# Power.net
KiCad netlist of a schematic drawn in Altium Designer
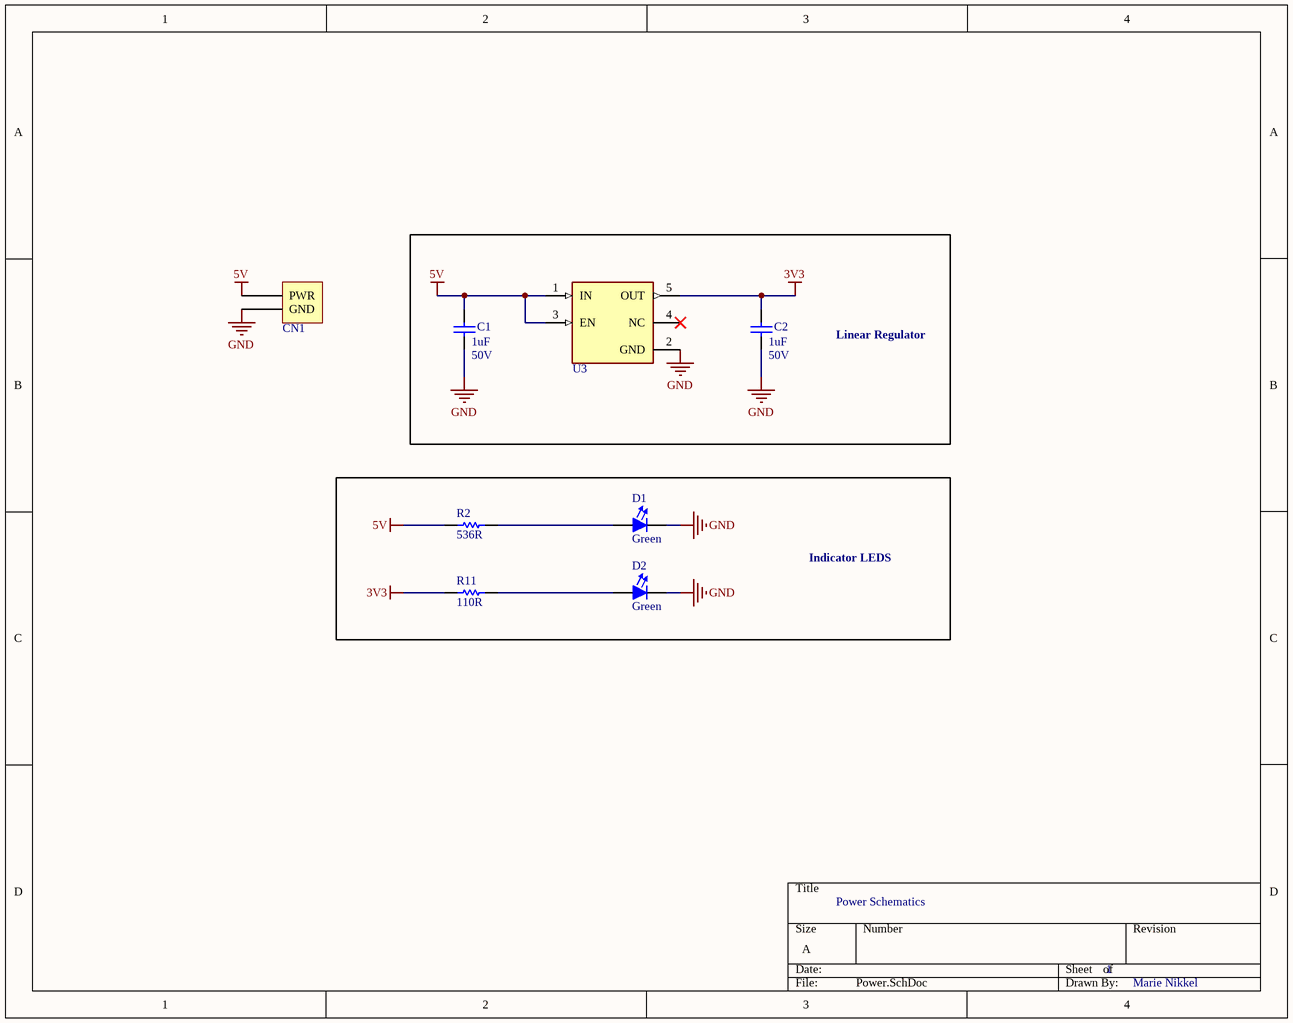
[diagram p0: Power.SchDoc]

(export (version "E")
  (design (tool "Eeschema 10.0.6"))
  (components
    (comp (ref "C1")
      (value "CL21B105KBFNNNG")
      (footprint "0803 CAP")
      (description "SAMSUNG ELECTRO-MECHANICS - CL21B105KBFNNNG - MLCC CAPACITORS")
      (fields
        (field (name "TOLERANCE") "10%")
        (field (name "CAPACITANCE") "1uF")
        (field (name "VOLTAGE") "50V")
      )
      (libsource (lib "AUVIC") (part "Symbol"))
    )
    (comp (ref "C2")
      (value "CL21B105KBFNNNG")
      (footprint "0803 CAP")
      (description "SAMSUNG ELECTRO-MECHANICS - CL21B105KBFNNNG - MLCC CAPACITORS")
      (fields
        (field (name "TOLERANCE") "10%")
        (field (name "CAPACITANCE") "1uF")
        (field (name "VOLTAGE") "50V")
      )
      (libsource (lib "AUVIC") (part "Symbol"))
    )
    (comp (ref "CN1")
      (value "Header, Female, 1x2, Right Angle, Pitch 0.118\" (3.00mm), THT")
      (footprint "New footprint 1")
      (description "Connector Header Through Hole, Right Angle 2 position")
      (libsource (lib "AUVIC") (part "Header, 1x2, Right Angle, Pitch 0.118{dblquote} (3.00mm), THT"))
    )
    (comp (ref "D1")
      (value "LT Q39G-Q1OO-25-1")
      (footprint "FP-LB_Q39E-MFG")
      (description "LED GREEN DIFFUSED 0603 SMD")
      (fields (field (name "COLOR") "Green"))
      (libsource (lib "") (part "Symbol_1"))
    )
    (comp (ref "D2")
      (value "LT Q39G-Q1OO-25-1")
      (footprint "FP-LB_Q39E-MFG")
      (description "LED GREEN DIFFUSED 0603 SMD")
      (fields (field (name "COLOR") "Green"))
      (libsource (lib "") (part "Symbol_1"))
    )
    (comp (ref "R2")
      (value "ERJ-3EKF5360V")
      (footprint "RESC1608X55X30NL15T15")
      (description "SMD Chip Resistor, 0603 [1608 Metric], 536 ohm, ERJ3EK Series, 75 V, Thick Film, 100 mW")
      (fields (field (name "TOLERANCE") "1%") (field (name "RESISTANCE") "536R"))
      (libsource (lib "AUVIC") (part "RES"))
    )
    (comp (ref "R11")
      (value "RC0603FR-07110RL")
      (footprint "RESC1608X55X25ML10T15")
      (description "RES SMD 110 OHM 1% 1/10W 0603")
      (fields (field (name "TOLERANCE") "1%") (field (name "RESISTANCE") "110R"))
      (libsource (lib "AUVIC") (part "RES"))
    )
    (comp (ref "U3")
      (value "TLV75533PDBVR")
      (footprint "FP-DBV0005A-IPC_B")
      (description "500-mA, high-PSRR, low-IQ, low-dropout voltage regulator with enable 5-SOT-23 -40 to 125")
      (libsource (lib "AUVIC") (part "bc27d4aa6bca38f00d7b0ca125c90e0"))
    )
  )
  (nets
    (net (code "1") (name "3V3") (class "Default")
      (node (ref "C2") (pin "1") (pinfunction "1_1") (pintype "passive"))
      (node (ref "R11") (pin "1") (pinfunction "1_1") (pintype "passive"))
      (node (ref "U3") (pin "5") (pinfunction "OUT_5") (pintype "output"))
    )
    (net (code "2") (name "5V") (class "Default")
      (node (ref "C1") (pin "1") (pinfunction "1_1") (pintype "passive"))
      (node (ref "CN1") (pin "2") (pinfunction "PWR_2") (pintype "passive"))
      (node (ref "R2") (pin "1") (pinfunction "1_1") (pintype "passive"))
      (node (ref "U3") (pin "1") (pinfunction "IN_1") (pintype "input"))
      (node (ref "U3") (pin "3") (pinfunction "EN_3") (pintype "input"))
    )
    (net (code "3") (name "GND") (class "Default")
      (node (ref "C1") (pin "2") (pinfunction "2_2") (pintype "passive"))
      (node (ref "C2") (pin "2") (pinfunction "2_2") (pintype "passive"))
      (node (ref "CN1") (pin "1") (pinfunction "GND_1") (pintype "passive"))
      (node (ref "D1") (pin "1") (pinfunction "Cathode_1") (pintype "passive"))
      (node (ref "D2") (pin "1") (pinfunction "Cathode_1") (pintype "passive"))
      (node (ref "U3") (pin "2") (pinfunction "GND_2") (pintype "power_in"))
    )
    (net (code "4") (name "Net-(D1-Anode)") (class "Default")
      (node (ref "D1") (pin "2") (pinfunction "Anode_2") (pintype "passive"))
      (node (ref "R2") (pin "2") (pinfunction "2_2") (pintype "passive"))
    )
    (net (code "5") (name "Net-(D2-Anode)") (class "Default")
      (node (ref "D2") (pin "2") (pinfunction "Anode_2") (pintype "passive"))
      (node (ref "R11") (pin "2") (pinfunction "2_2") (pintype "passive"))
    )
    (net (code "6") (name "unconnected-(U3-NC-Pad4)") (class "Default")
      (node (ref "U3") (pin "4") (pinfunction "NC_4") (pintype "passive+no_connect"))
    )
  )
)
